# SCH_WETBCV1XX.net
KiCad netlist of a schematic drawn in Altium Designer
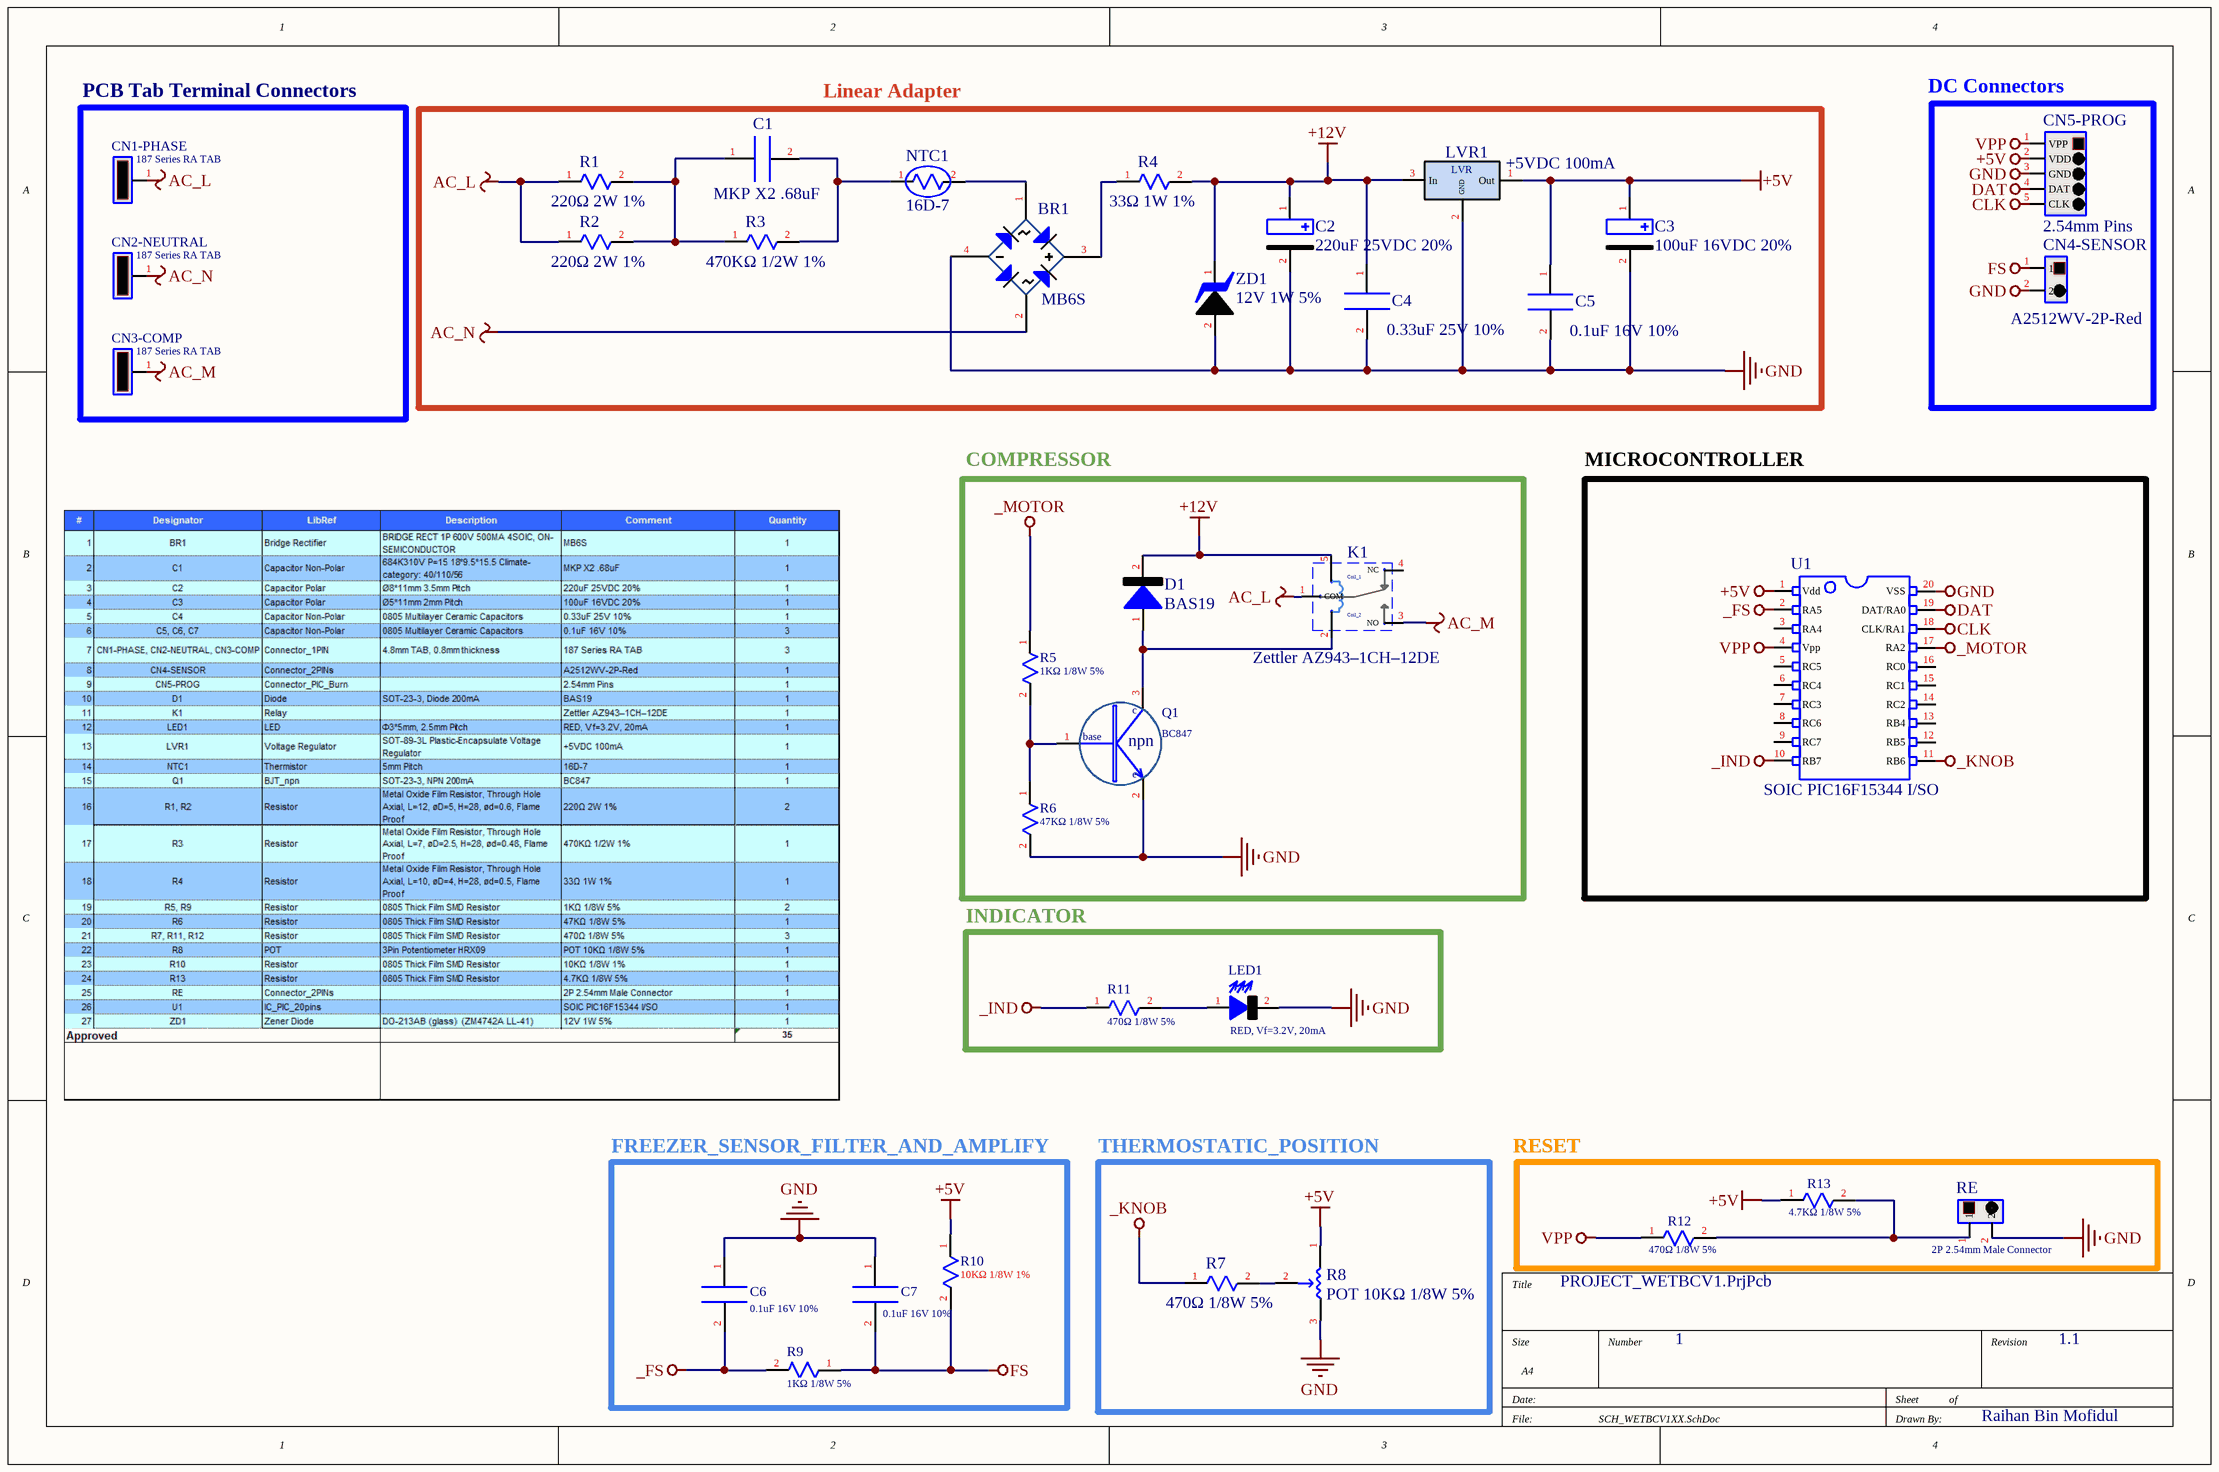
[diagram p0: SCH_WETBCV1XX.SchDoc]

(export (version "E")
  (design (tool "Eeschema 10.0.6"))
  (components
    (comp (ref "BR1")
      (value "MB6S")
      (footprint "BR_SMD_MB6S")
      (description "BRIDGE RECT 1P 600V 500MA 4SOIC, ON-SEMICONDUCTOR")
      (libsource (lib "RBM_SCH-LIB_02-SEP-19") (part "Bridge Rectifier"))
    )
    (comp (ref "C1")
      (value "MKP X2 .68uF")
      (footprint "C_X2_18X10X15.8_P15")
      (description "684K310V P=15 18*9.5*15.5 Climate-category: 40/110/56")
      (libsource (lib "RBM_SCH-LIB_02-SEP-19") (part "Capacitor Non-Polar"))
    )
    (comp (ref "C2")
      (value "220uF 25VDC 20%")
      (footprint "C_Radial_P3.5")
      (description "Ø8*11mm 3.5mm Pitch")
      (libsource (lib "RBM_SCH-LIB_02-SEP-19") (part "Capacitor Polar"))
    )
    (comp (ref "C3")
      (value "100uF 16VDC 20%")
      (footprint "C_Radial_P2")
      (description "Ø5*11mm 2mm Pitch")
      (libsource (lib "RBM_SCH-LIB_02-SEP-19") (part "Capacitor Polar"))
    )
    (comp (ref "C4")
      (value "0.33uF 25V 10%")
      (footprint "C_0805")
      (description "0805 Multilayer Ceramic Capacitors")
      (libsource (lib "RBM_SCH-Lib_16-Apr-19") (part "Capacitor Non-Polar"))
    )
    (comp (ref "C5")
      (value "0.1uF 16V 10%")
      (footprint "C_0805")
      (description "0805 Multilayer Ceramic Capacitors")
      (libsource (lib "RBM_SCH-Lib_16-Apr-19") (part "Capacitor Non-Polar"))
    )
    (comp (ref "C6")
      (value "0.1uF 16V 10%")
      (footprint "C_0805")
      (description "0805 Multilayer Ceramic Capacitors")
      (libsource (lib "RBM_SCH-Lib_16-Apr-19") (part "Capacitor Non-Polar"))
    )
    (comp (ref "C7")
      (value "0.1uF 16V 10%")
      (footprint "C_0805")
      (description "0805 Multilayer Ceramic Capacitors")
      (libsource (lib "RBM_SCH-Lib_16-Apr-19") (part "Capacitor Non-Polar"))
    )
    (comp (ref "CN1-PHASE")
      (value "187 Series RA TAB")
      (footprint "CN_Tab Terminal 187 series (Right Angle)")
      (description "4.8mm TAB, 0.8mm thickness")
      (libsource (lib "RBM_SCH-LIB_02-SEP-19") (part "Connector_1PIN"))
    )
    (comp (ref "CN2-NEUTRAL")
      (value "187 Series RA TAB")
      (footprint "CN_Tab Terminal 187 series (Right Angle)")
      (description "4.8mm TAB, 0.8mm thickness")
      (libsource (lib "RBM_SCH-LIB_02-SEP-19") (part "Connector_1PIN"))
    )
    (comp (ref "CN3-COMP")
      (value "187 Series RA TAB")
      (footprint "CN_Tab Terminal 187 series (Right Angle)")
      (description "4.8mm TAB, 0.8mm thickness")
      (libsource (lib "RBM_SCH-LIB_02-SEP-19") (part "Connector_1PIN"))
    )
    (comp (ref "CN4-SENSOR")
      (value "A2512WV-2P-Red")
      (footprint "CN_B2B-XH-A_WHITE")
      (libsource (lib "RBM_SCH-Lib_16-Apr-19") (part "Connector_2PINs"))
    )
    (comp (ref "CN5-PROG")
      (value "2.54mm Pins")
      (footprint "CN_PIC_MCU_Debugger_Straight")
      (libsource (lib "RBM_SCH-Lib_16-Apr-19") (part "Connector_PIC_Burn"))
    )
    (comp (ref "D1")
      (value "BAS19")
      (footprint "D_SOT-23-3_200mA")
      (description "SOT-23-3, Diode 200mA")
      (libsource (lib "RBM_SCH-LIB_02-SEP-19") (part "Diode"))
    )
    (comp (ref "K1")
      (value "Zettler AZ943–1CH–12DE")
      (footprint "K_15ARelay_AZ943-1CH-12DE")
      (libsource (lib "RBM_SCH-Lib_16-Apr-19") (part "Relay"))
    )
    (comp (ref "LED1")
      (value "RED, Vf=3.2V, 20mA")
      (footprint "LED_3x5_P2.5")
      (description "Φ3*5mm, 2.5mm Pitch")
      (libsource (lib "RBM_SCH-LIB_02-SEP-19") (part "LED"))
    )
    (comp (ref "LVR1")
      (value "+5VDC 100mA")
      (footprint "U_CJ78L05_SOT89")
      (description "SOT-89-3L Plastic-Encapsulate Voltage Regulator")
      (libsource (lib "RBM_SCH-Lib_16-Apr-19") (part "Voltage Regulator"))
    )
    (comp (ref "NTC1")
      (value "16D-7")
      (footprint "NTC_5mmPitch")
      (description "5mm Pitch")
      (libsource (lib "RBM_SCH-LIB_02-SEP-19") (part "Thermistor"))
    )
    (comp (ref "Q1")
      (value "BC847")
      (footprint "Q_SOT-23-3_NPN_BC847")
      (description "SOT-23-3, NPN 200mA")
      (libsource (lib "RBM_SCH-Lib_16-Apr-19") (part "BJT_npn"))
    )
    (comp (ref "R1")
      (value "220Ω 2W 1%")
      (footprint "R_Axial_P15")
      (description "Metal Oxide Film Resistor, Through Hole Axial, L=12, øD=5, H=28, ød=0.6, Flame Proof")
      (libsource (lib "RBM_SCH-LIB_02-SEP-19") (part "Resistor"))
    )
    (comp (ref "R2")
      (value "220Ω 2W 1%")
      (footprint "R_Axial_P15")
      (description "Metal Oxide Film Resistor, Through Hole Axial, L=12, øD=5, H=28, ød=0.6, Flame Proof")
      (libsource (lib "RBM_SCH-LIB_02-SEP-19") (part "Resistor"))
    )
    (comp (ref "R3")
      (value "470KΩ 1/2W 1%")
      (footprint "R_Axial_P10")
      (description "Metal Oxide Film Resistor, Through Hole Axial, L=7, øD=2.5, H=28, ød=0.48, Flame Proof")
      (libsource (lib "RBM_SCH-LIB_02-SEP-19") (part "Resistor"))
    )
    (comp (ref "R4")
      (value "33Ω 1W 1%")
      (footprint "R_Axial_P15")
      (description "Metal Oxide Film Resistor, Through Hole Axial, L=10, øD=4, H=28, ød=0.5, Flame Proof")
      (libsource (lib "RBM_SCH-LIB_02-SEP-19") (part "Resistor"))
    )
    (comp (ref "R5")
      (value "1KΩ 1/8W 5%")
      (footprint "R_0805")
      (description "0805 Thick Film SMD Resistor")
      (libsource (lib "RBM_SCH-Lib_16-Apr-19") (part "Resistor"))
    )
    (comp (ref "R6")
      (value "47KΩ 1/8W 5%")
      (footprint "R_0805")
      (description "0805 Thick Film SMD Resistor")
      (libsource (lib "RBM_SCH-Lib_16-Apr-19") (part "Resistor"))
    )
    (comp (ref "R7")
      (value "470Ω 1/8W 5%")
      (footprint "R_0805")
      (description "0805 Thick Film SMD Resistor")
      (libsource (lib "RBM_SCH-LIB_02-SEP-19") (part "Resistor"))
    )
    (comp (ref "R8")
      (value "POT 10KΩ 1/8W 5%")
      (footprint "R_POT")
      (description "3Pin Potentiometer HRX09")
      (libsource (lib "RBM_SCH-LIB_02-SEP-19") (part "POT"))
    )
    (comp (ref "R9")
      (value "1KΩ 1/8W 5%")
      (footprint "R_0805")
      (description "0805 Thick Film SMD Resistor")
      (libsource (lib "RBM_SCH-Lib_16-Apr-19") (part "Resistor"))
    )
    (comp (ref "R10")
      (value "10KΩ 1/8W 1%")
      (footprint "R_0805")
      (description "0805 Thick Film SMD Resistor")
      (libsource (lib "RBM_SCH-Lib_16-Apr-19") (part "Resistor"))
    )
    (comp (ref "R11")
      (value "470Ω 1/8W 5%")
      (footprint "R_0805")
      (description "0805 Thick Film SMD Resistor")
      (libsource (lib "RBM_SCH-Lib_16-Apr-19") (part "Resistor"))
    )
    (comp (ref "R12")
      (value "470Ω 1/8W 5%")
      (footprint "R_0805")
      (description "0805 Thick Film SMD Resistor")
      (libsource (lib "RBM_SCH-Lib_16-Apr-19") (part "Resistor"))
    )
    (comp (ref "R13")
      (value "4.7KΩ 1/8W 5%")
      (footprint "R_0805")
      (description "0805 Thick Film SMD Resistor")
      (libsource (lib "RBM_SCH-Lib_16-Apr-19") (part "Resistor"))
    )
    (comp (ref "RE")
      (value "2P 2.54mm Male Connector")
      (footprint "CN_PIC_MCU_Reseter_Straight")
      (libsource (lib "RBM_SCH-LIB_02-SEP-19") (part "Connector_2PINs"))
    )
    (comp (ref "U1")
      (value "SOIC PIC16F15344 I/SO")
      (footprint "U_PIC16F15344_SOIC")
      (libsource (lib "RBM_SCH-Lib_16-Apr-19") (part "IC_PIC_20pins"))
    )
    (comp (ref "ZD1")
      (value "12V 1W 5%")
      (footprint "ZD_ZM4742A LL-41")
      (description "DO-213AB (glass)  (ZM4742A LL-41)")
      (libsource (lib "RBM_SCH-LIB_02-SEP-19") (part "Zener Diode"))
    )
  )
  (nets
    (net (code "1") (name "+5V") (class "Default")
      (node (ref "C3") (pin "1") (pinfunction "vdd_1") (pintype "passive"))
      (node (ref "C5") (pin "1") (pinfunction "1_1") (pintype "passive"))
      (node (ref "CN5-PROG") (pin "2") (pinfunction "VDD_2") (pintype "passive"))
      (node (ref "LVR1") (pin "1") (pinfunction "Out_1") (pintype "passive"))
      (node (ref "R10") (pin "1") (pinfunction "1_1") (pintype "passive"))
      (node (ref "R13") (pin "1") (pinfunction "1_1") (pintype "passive"))
      (node (ref "R8") (pin "1") (pinfunction "VDD_1") (pintype "passive"))
      (node (ref "U1") (pin "1") (pinfunction "Vdd_1") (pintype "passive"))
    )
    (net (code "2") (name "+12V") (class "Default")
      (node (ref "C2") (pin "1") (pinfunction "vdd_1") (pintype "passive"))
      (node (ref "C4") (pin "1") (pinfunction "1_1") (pintype "passive"))
      (node (ref "D1") (pin "2") (pinfunction "vss_2") (pintype "passive"))
      (node (ref "K1") (pin "5") (pinfunction "COIL1_5") (pintype "passive"))
      (node (ref "LVR1") (pin "3") (pinfunction "In_3") (pintype "passive"))
      (node (ref "R4") (pin "2") (pinfunction "2_2") (pintype "passive"))
      (node (ref "ZD1") (pin "1") (pinfunction "VCC_1") (pintype "passive"))
    )
    (net (code "3") (name "AC_L") (class "Default")
      (node (ref "CN1-PHASE") (pin "1") (pinfunction "1_1") (pintype "passive"))
      (node (ref "K1") (pin "1") (pinfunction "COM_1") (pintype "passive"))
      (node (ref "R1") (pin "1") (pinfunction "1_1") (pintype "passive"))
      (node (ref "R2") (pin "1") (pinfunction "1_1") (pintype "passive"))
    )
    (net (code "4") (name "AC_M") (class "Default")
      (node (ref "CN3-COMP") (pin "1") (pinfunction "1_1") (pintype "passive"))
      (node (ref "K1") (pin "3") (pinfunction "NO_3") (pintype "passive"))
    )
    (net (code "5") (name "AC_N") (class "Default")
      (node (ref "BR1") (pin "2") (pinfunction "AC_2") (pintype "passive"))
      (node (ref "CN2-NEUTRAL") (pin "1") (pinfunction "1_1") (pintype "passive"))
    )
    (net (code "6") (name "CLK") (class "Default")
      (node (ref "CN5-PROG") (pin "5") (pinfunction "CLK_5") (pintype "passive"))
      (node (ref "U1") (pin "18") (pinfunction "CLK/RA1_18") (pintype "passive"))
    )
    (net (code "7") (name "DAT") (class "Default")
      (node (ref "CN5-PROG") (pin "4") (pinfunction "DAT_4") (pintype "passive"))
      (node (ref "U1") (pin "19") (pinfunction "DAT/RA0_19") (pintype "passive"))
    )
    (net (code "8") (name "FS") (class "Default")
      (node (ref "C7") (pin "2") (pinfunction "2_2") (pintype "passive"))
      (node (ref "CN4-SENSOR") (pin "1") (pinfunction "1_1") (pintype "passive"))
      (node (ref "R10") (pin "2") (pinfunction "2_2") (pintype "passive"))
      (node (ref "R9") (pin "1") (pinfunction "1_1") (pintype "passive"))
    )
    (net (code "9") (name "GND") (class "Default")
      (node (ref "BR1") (pin "4") (pinfunction "vss_4") (pintype "passive"))
      (node (ref "C2") (pin "2") (pinfunction "vss_2") (pintype "passive"))
      (node (ref "C3") (pin "2") (pinfunction "vss_2") (pintype "passive"))
      (node (ref "C4") (pin "2") (pinfunction "2_2") (pintype "passive"))
      (node (ref "C5") (pin "2") (pinfunction "2_2") (pintype "passive"))
      (node (ref "C6") (pin "1") (pinfunction "1_1") (pintype "passive"))
      (node (ref "C7") (pin "1") (pinfunction "1_1") (pintype "passive"))
      (node (ref "CN4-SENSOR") (pin "2") (pinfunction "2_2") (pintype "passive"))
      (node (ref "CN5-PROG") (pin "3") (pinfunction "GND_3") (pintype "passive"))
      (node (ref "LED1") (pin "2") (pinfunction "vss_2") (pintype "passive"))
      (node (ref "LVR1") (pin "2") (pinfunction "GND_2") (pintype "passive"))
      (node (ref "Q1") (pin "2") (pinfunction "Emitter_2") (pintype "passive"))
      (node (ref "R6") (pin "2") (pinfunction "2_2") (pintype "passive"))
      (node (ref "R8") (pin "3") (pinfunction "VSS_3") (pintype "passive"))
      (node (ref "RE") (pin "2") (pinfunction "2_2") (pintype "passive"))
      (node (ref "U1") (pin "20") (pinfunction "VSS_20") (pintype "passive"))
      (node (ref "ZD1") (pin "2") (pinfunction "GND_2") (pintype "passive"))
    )
    (net (code "10") (name "Net-(BR1-AC-Pad1)") (class "Default")
      (node (ref "BR1") (pin "1") (pinfunction "AC_1") (pintype "passive"))
      (node (ref "NTC1") (pin "2") (pinfunction "2_2") (pintype "passive"))
    )
    (net (code "11") (name "Net-(BR1-VCC)") (class "Default")
      (node (ref "BR1") (pin "3") (pinfunction "VCC_3") (pintype "passive"))
      (node (ref "R4") (pin "1") (pinfunction "1_1") (pintype "passive"))
    )
    (net (code "12") (name "Net-(C1-Pad1)") (class "Default")
      (node (ref "C1") (pin "1") (pinfunction "1_1") (pintype "passive"))
      (node (ref "R1") (pin "2") (pinfunction "2_2") (pintype "passive"))
      (node (ref "R2") (pin "2") (pinfunction "2_2") (pintype "passive"))
      (node (ref "R3") (pin "1") (pinfunction "1_1") (pintype "passive"))
    )
    (net (code "13") (name "Net-(C1-Pad2)") (class "Default")
      (node (ref "C1") (pin "2") (pinfunction "2_2") (pintype "passive"))
      (node (ref "NTC1") (pin "1") (pinfunction "1_1") (pintype "passive"))
      (node (ref "R3") (pin "2") (pinfunction "2_2") (pintype "passive"))
    )
    (net (code "14") (name "Net-(D1-vdd)") (class "Default")
      (node (ref "D1") (pin "1") (pinfunction "vdd_1") (pintype "passive"))
      (node (ref "K1") (pin "2") (pinfunction "COIL2_2") (pintype "passive"))
      (node (ref "Q1") (pin "3") (pinfunction "Collector_3") (pintype "passive"))
    )
    (net (code "15") (name "Net-(LED1-vdd)") (class "Default")
      (node (ref "LED1") (pin "1") (pinfunction "vdd_1") (pintype "passive"))
      (node (ref "R11") (pin "2") (pinfunction "2_2") (pintype "passive"))
    )
    (net (code "16") (name "Net-(Q1-Base)") (class "Default")
      (node (ref "Q1") (pin "1") (pinfunction "Base_1") (pintype "passive"))
      (node (ref "R5") (pin "2") (pinfunction "2_2") (pintype "passive"))
      (node (ref "R6") (pin "1") (pinfunction "1_1") (pintype "passive"))
    )
    (net (code "17") (name "Net-(R8-POT)") (class "Default")
      (node (ref "R7") (pin "2") (pinfunction "2_2") (pintype "passive"))
      (node (ref "R8") (pin "2") (pinfunction "POT_2") (pintype "passive"))
    )
    (net (code "18") (name "Net-(R12-Pad2)") (class "Default")
      (node (ref "R12") (pin "2") (pinfunction "2_2") (pintype "passive"))
      (node (ref "R13") (pin "2") (pinfunction "2_2") (pintype "passive"))
      (node (ref "RE") (pin "1") (pinfunction "1_1") (pintype "passive"))
    )
    (net (code "19") (name "VPP") (class "Default")
      (node (ref "CN5-PROG") (pin "1") (pinfunction "VPP_1") (pintype "passive"))
      (node (ref "R12") (pin "1") (pinfunction "1_1") (pintype "passive"))
      (node (ref "U1") (pin "4") (pinfunction "Vpp_4") (pintype "passive"))
    )
    (net (code "20") (name "_FS") (class "Default")
      (node (ref "C6") (pin "2") (pinfunction "2_2") (pintype "passive"))
      (node (ref "R9") (pin "2") (pinfunction "2_2") (pintype "passive"))
      (node (ref "U1") (pin "2") (pinfunction "RA5_2") (pintype "passive"))
    )
    (net (code "21") (name "_IND") (class "Default")
      (node (ref "R11") (pin "1") (pinfunction "1_1") (pintype "passive"))
      (node (ref "U1") (pin "10") (pinfunction "RB7_10") (pintype "passive"))
    )
    (net (code "22") (name "_KNOB") (class "Default")
      (node (ref "R7") (pin "1") (pinfunction "1_1") (pintype "passive"))
      (node (ref "U1") (pin "11") (pinfunction "RB6_11") (pintype "passive"))
    )
    (net (code "23") (name "_MOTOR") (class "Default")
      (node (ref "R5") (pin "1") (pinfunction "1_1") (pintype "passive"))
      (node (ref "U1") (pin "17") (pinfunction "RA2_17") (pintype "passive"))
    )
    (net (code "24") (name "unconnected-(K1-NC-Pad4)") (class "Default")
      (node (ref "K1") (pin "4") (pinfunction "NC_4") (pintype "passive"))
    )
    (net (code "25") (name "unconnected-(U1-RA4-Pad3)") (class "Default")
      (node (ref "U1") (pin "3") (pinfunction "RA4_3") (pintype "passive"))
    )
    (net (code "26") (name "unconnected-(U1-RB4-Pad13)") (class "Default")
      (node (ref "U1") (pin "13") (pinfunction "RB4_13") (pintype "passive"))
    )
    (net (code "27") (name "unconnected-(U1-RB5-Pad12)") (class "Default")
      (node (ref "U1") (pin "12") (pinfunction "RB5_12") (pintype "passive"))
    )
    (net (code "28") (name "unconnected-(U1-RC0-Pad16)") (class "Default")
      (node (ref "U1") (pin "16") (pinfunction "RC0_16") (pintype "passive"))
    )
    (net (code "29") (name "unconnected-(U1-RC1-Pad15)") (class "Default")
      (node (ref "U1") (pin "15") (pinfunction "RC1_15") (pintype "passive"))
    )
    (net (code "30") (name "unconnected-(U1-RC2-Pad14)") (class "Default")
      (node (ref "U1") (pin "14") (pinfunction "RC2_14") (pintype "passive"))
    )
    (net (code "31") (name "unconnected-(U1-RC3-Pad7)") (class "Default")
      (node (ref "U1") (pin "7") (pinfunction "RC3_7") (pintype "passive"))
    )
    (net (code "32") (name "unconnected-(U1-RC4-Pad6)") (class "Default")
      (node (ref "U1") (pin "6") (pinfunction "RC4_6") (pintype "passive"))
    )
    (net (code "33") (name "unconnected-(U1-RC5-Pad5)") (class "Default")
      (node (ref "U1") (pin "5") (pinfunction "RC5_5") (pintype "passive"))
    )
    (net (code "34") (name "unconnected-(U1-RC6-Pad8)") (class "Default")
      (node (ref "U1") (pin "8") (pinfunction "RC6_8") (pintype "passive"))
    )
    (net (code "35") (name "unconnected-(U1-RC7-Pad9)") (class "Default")
      (node (ref "U1") (pin "9") (pinfunction "RC7_9") (pintype "passive"))
    )
  )
)
